# Schaltplan_Mark4.net
KiCad netlist of a schematic drawn in EAGLE
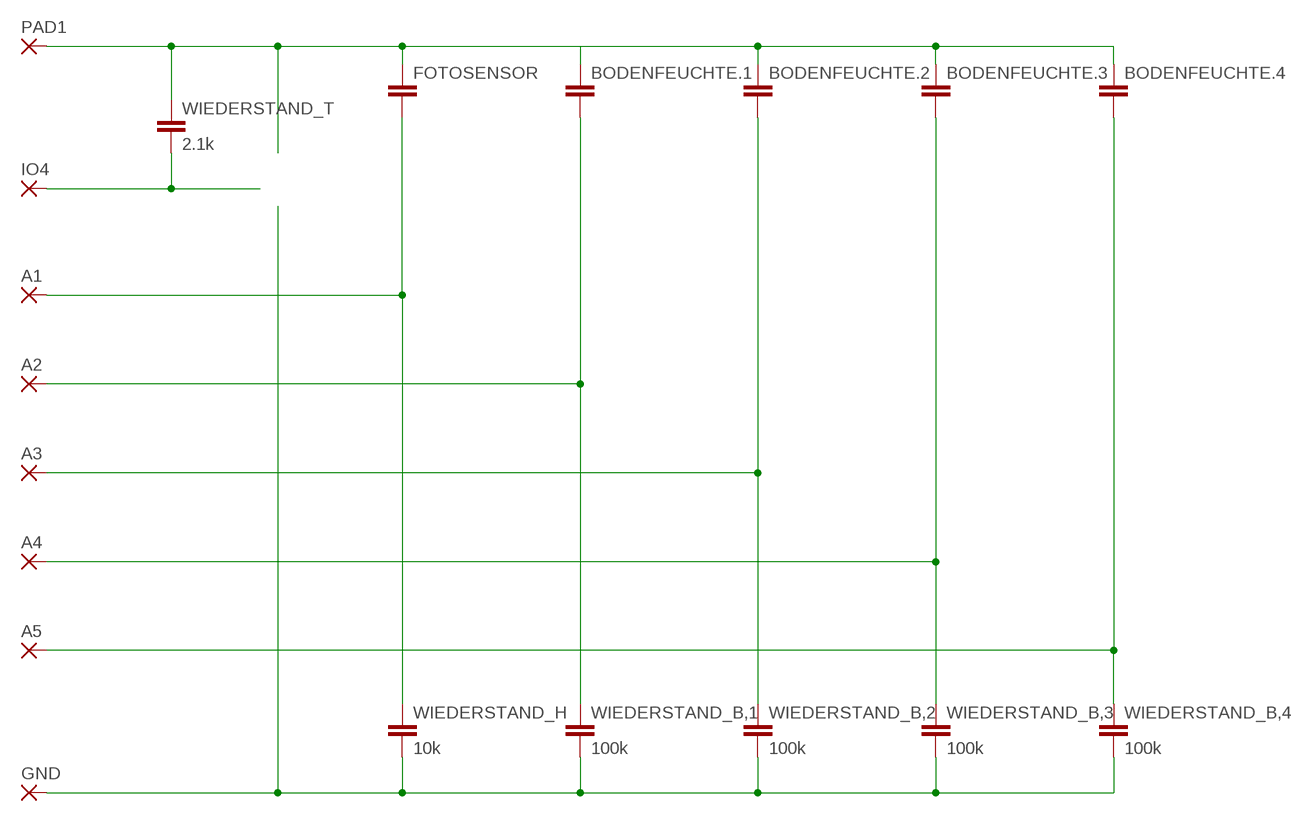
[diagram p0: schematic, sheet 1]

(export (version "E")
  (design (tool "Eeschema 10.0.6"))
  (components
    (comp (ref "A1")
      (value "SMD2")
      (footprint "eagle-import:SMD1,27-2,54")
      (libsource (lib "eagle-import") (part "SMD2"))
    )
    (comp (ref "A2")
      (value "SMD2")
      (footprint "eagle-import:SMD1,27-2,54")
      (libsource (lib "eagle-import") (part "SMD2"))
    )
    (comp (ref "A3")
      (value "SMD2")
      (footprint "eagle-import:SMD1,27-2,54")
      (libsource (lib "eagle-import") (part "SMD2"))
    )
    (comp (ref "A4")
      (value "SMD2")
      (footprint "eagle-import:SMD1,27-2,54")
      (libsource (lib "eagle-import") (part "SMD2"))
    )
    (comp (ref "A5")
      (value "SMD2")
      (footprint "eagle-import:SMD1,27-2,54")
      (libsource (lib "eagle-import") (part "SMD2"))
    )
    (comp (ref "BODENFEUCHTE.1")
      (value "C-EU050-024X044")
      (footprint "eagle-import:C050-024X044")
      (libsource (lib "eagle-import") (part "C-EU050-024X044"))
    )
    (comp (ref "BODENFEUCHTE.2")
      (value "C-EU050-024X044")
      (footprint "eagle-import:C050-024X044")
      (libsource (lib "eagle-import") (part "C-EU050-024X044"))
    )
    (comp (ref "BODENFEUCHTE.3")
      (value "C-EU050-024X044")
      (footprint "eagle-import:C050-024X044")
      (libsource (lib "eagle-import") (part "C-EU050-024X044"))
    )
    (comp (ref "BODENFEUCHTE.4")
      (value "C-EU050-024X044")
      (footprint "eagle-import:C050-024X044")
      (libsource (lib "eagle-import") (part "C-EU050-024X044"))
    )
    (comp (ref "FOTOSENSOR")
      (value "C-EU050-024X044")
      (footprint "eagle-import:C050-024X044")
      (libsource (lib "eagle-import") (part "C-EU050-024X044"))
    )
    (comp (ref "GND")
      (value "SMD2")
      (footprint "eagle-import:SMD1,27-2,54")
      (libsource (lib "eagle-import") (part "SMD2"))
    )
    (comp (ref "IO4")
      (value "SMD2")
      (footprint "eagle-import:SMD1,27-2,54")
      (libsource (lib "eagle-import") (part "SMD2"))
    )
    (comp (ref "PAD1")
      (value "SMD2")
      (footprint "eagle-import:SMD1,27-2,54")
      (libsource (lib "eagle-import") (part "SMD2"))
    )
    (comp (ref "WIEDERSTAND_B,1")
      (value "100k")
      (footprint "eagle-import:C050-024X044")
      (libsource (lib "eagle-import") (part "C-EU050-024X044"))
    )
    (comp (ref "WIEDERSTAND_B,2")
      (value "100k")
      (footprint "eagle-import:C050-024X044")
      (libsource (lib "eagle-import") (part "C-EU050-024X044"))
    )
    (comp (ref "WIEDERSTAND_B,3")
      (value "100k")
      (footprint "eagle-import:C050-024X044")
      (libsource (lib "eagle-import") (part "C-EU050-024X044"))
    )
    (comp (ref "WIEDERSTAND_B,4")
      (value "100k")
      (footprint "eagle-import:C050-024X044")
      (libsource (lib "eagle-import") (part "C-EU050-024X044"))
    )
    (comp (ref "WIEDERSTAND_H")
      (value "10k")
      (footprint "eagle-import:C050-024X044")
      (libsource (lib "eagle-import") (part "C-EU050-024X044"))
    )
    (comp (ref "WIEDERSTAND_T")
      (value "2.1k")
      (footprint "eagle-import:C050-024X044")
      (libsource (lib "eagle-import") (part "C-EU050-024X044"))
    )
  )
  (nets
    (net (code "1") (name "Net-(A1-P)") (class "Default")
      (node (ref "A1") (pin "1") (pinfunction "P_1") (pintype "passive"))
      (node (ref "FOTOSENSOR") (pin "2") (pinfunction "2_2") (pintype "passive"))
      (node (ref "WIEDERSTAND_H") (pin "1") (pinfunction "1_1") (pintype "passive"))
    )
    (net (code "2") (name "Net-(A2-P)") (class "Default")
      (node (ref "A2") (pin "1") (pinfunction "P_1") (pintype "passive"))
      (node (ref "BODENFEUCHTE.1") (pin "2") (pinfunction "2_2") (pintype "passive"))
      (node (ref "WIEDERSTAND_B,1") (pin "1") (pinfunction "1_1") (pintype "passive"))
    )
    (net (code "3") (name "Net-(A3-P)") (class "Default")
      (node (ref "A3") (pin "1") (pinfunction "P_1") (pintype "passive"))
      (node (ref "BODENFEUCHTE.2") (pin "2") (pinfunction "2_2") (pintype "passive"))
      (node (ref "WIEDERSTAND_B,2") (pin "1") (pinfunction "1_1") (pintype "passive"))
    )
    (net (code "4") (name "Net-(A4-P)") (class "Default")
      (node (ref "A4") (pin "1") (pinfunction "P_1") (pintype "passive"))
      (node (ref "BODENFEUCHTE.3") (pin "2") (pinfunction "2_2") (pintype "passive"))
      (node (ref "WIEDERSTAND_B,3") (pin "1") (pinfunction "1_1") (pintype "passive"))
    )
    (net (code "5") (name "Net-(A5-P)") (class "Default")
      (node (ref "A5") (pin "1") (pinfunction "P_1") (pintype "passive"))
      (node (ref "BODENFEUCHTE.4") (pin "2") (pinfunction "2_2") (pintype "passive"))
      (node (ref "WIEDERSTAND_B,4") (pin "1") (pinfunction "1_1") (pintype "passive"))
    )
    (net (code "6") (name "Net-(GND-P)") (class "Default")
      (node (ref "GND") (pin "1") (pinfunction "P_1") (pintype "passive"))
      (node (ref "WIEDERSTAND_B,1") (pin "2") (pinfunction "2_2") (pintype "passive"))
      (node (ref "WIEDERSTAND_B,2") (pin "2") (pinfunction "2_2") (pintype "passive"))
      (node (ref "WIEDERSTAND_B,3") (pin "2") (pinfunction "2_2") (pintype "passive"))
      (node (ref "WIEDERSTAND_B,4") (pin "2") (pinfunction "2_2") (pintype "passive"))
      (node (ref "WIEDERSTAND_H") (pin "2") (pinfunction "2_2") (pintype "passive"))
    )
    (net (code "7") (name "Net-(IO4-P)") (class "Default")
      (node (ref "IO4") (pin "1") (pinfunction "P_1") (pintype "passive"))
      (node (ref "WIEDERSTAND_T") (pin "2") (pinfunction "2_2") (pintype "passive"))
    )
    (net (code "8") (name "Net-(PAD1-P)") (class "Default")
      (node (ref "BODENFEUCHTE.1") (pin "1") (pinfunction "1_1") (pintype "passive"))
      (node (ref "BODENFEUCHTE.2") (pin "1") (pinfunction "1_1") (pintype "passive"))
      (node (ref "BODENFEUCHTE.3") (pin "1") (pinfunction "1_1") (pintype "passive"))
      (node (ref "BODENFEUCHTE.4") (pin "1") (pinfunction "1_1") (pintype "passive"))
      (node (ref "FOTOSENSOR") (pin "1") (pinfunction "1_1") (pintype "passive"))
      (node (ref "PAD1") (pin "1") (pinfunction "P_1") (pintype "passive"))
      (node (ref "WIEDERSTAND_T") (pin "1") (pinfunction "1_1") (pintype "passive"))
    )
  )
)
